# BSPD_rev11_v2.net
KiCad netlist of a schematic drawn in EAGLE
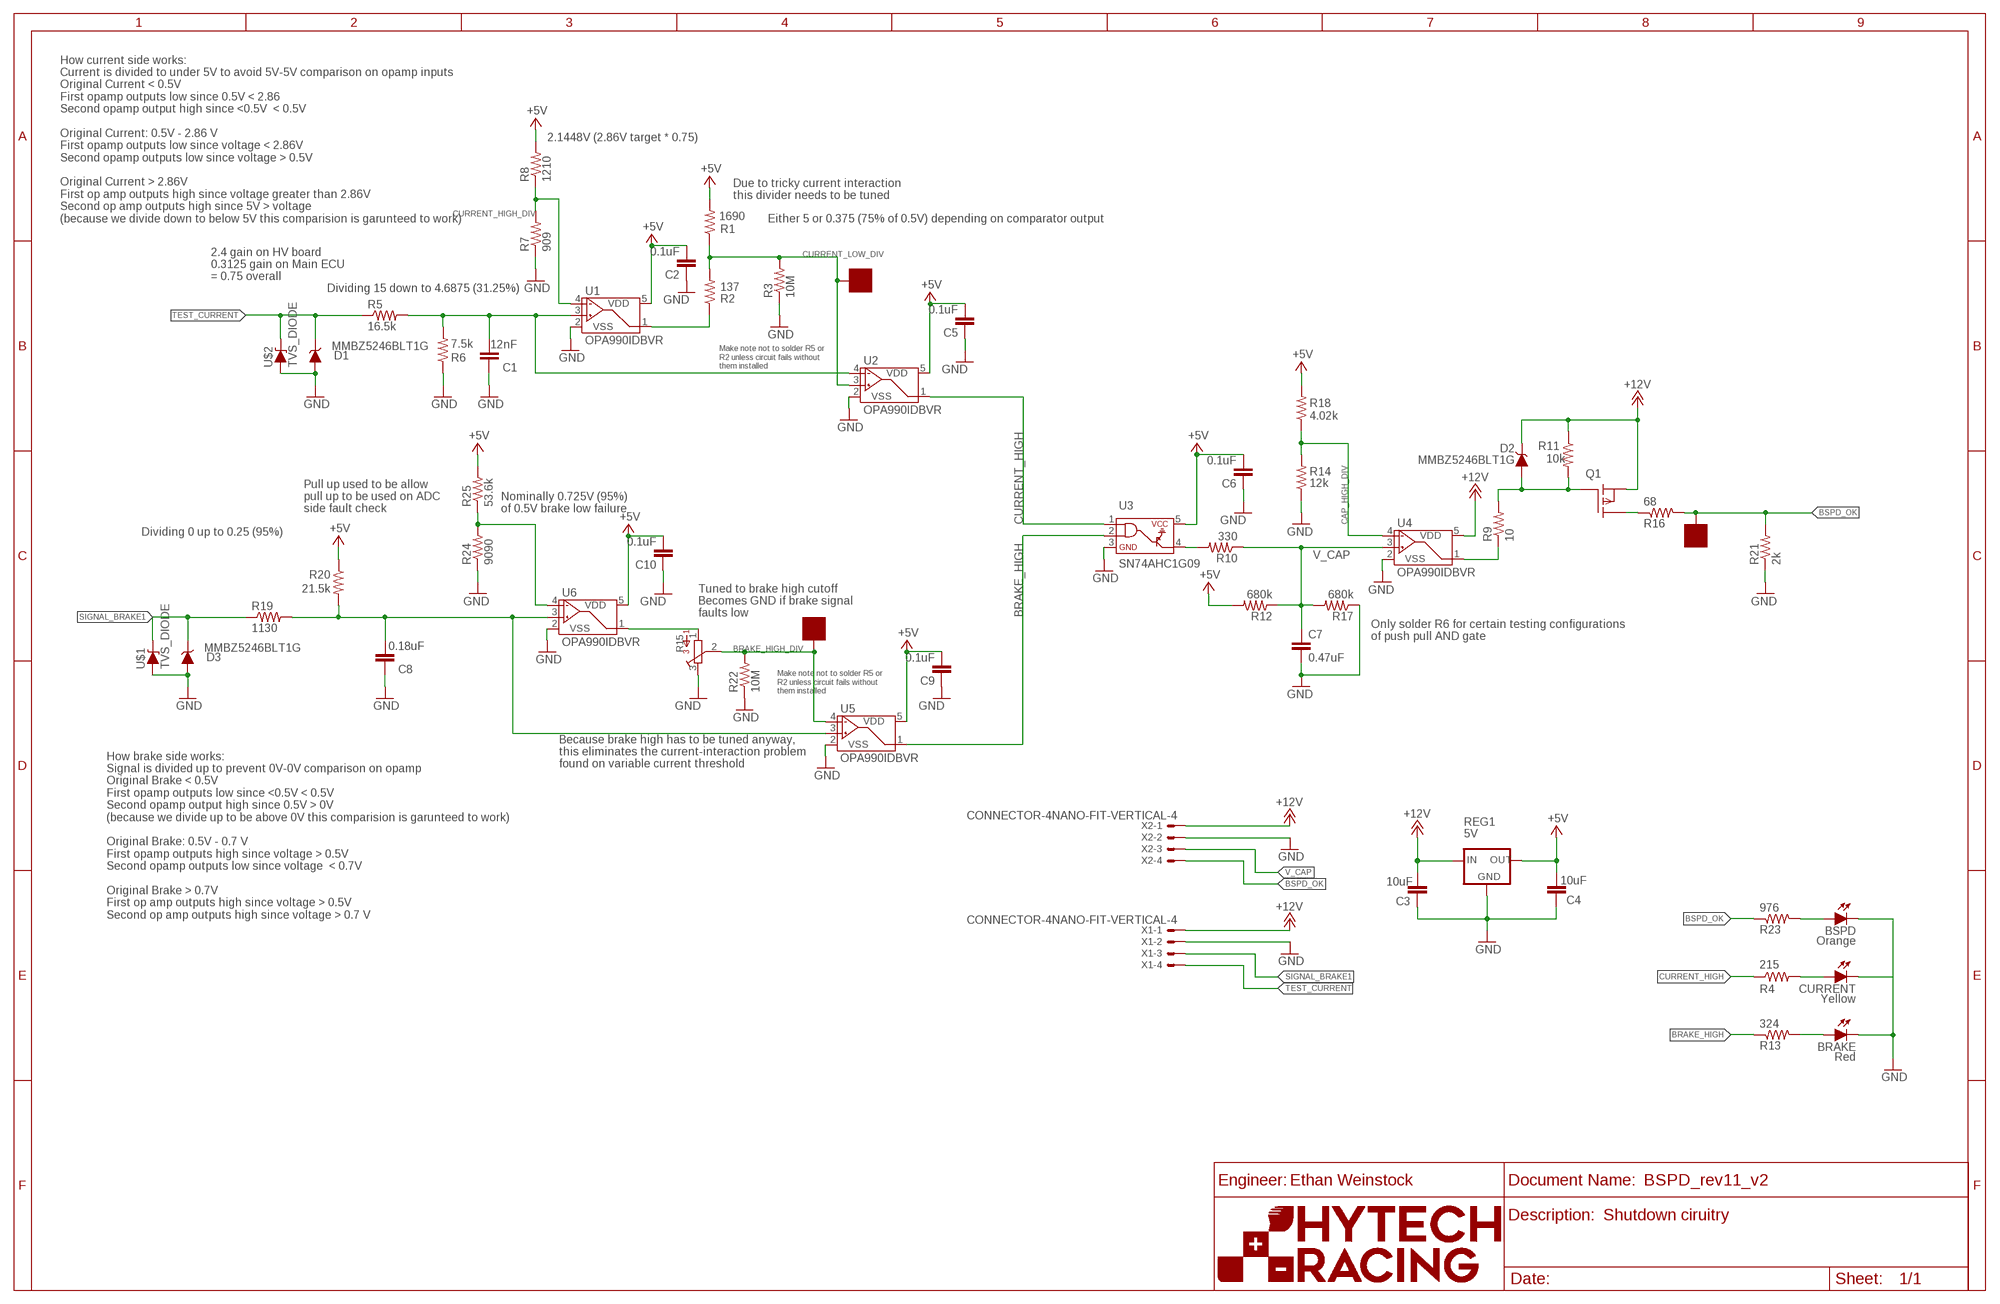
[diagram p0: schematic, sheet 1]

(export (version "E")
  (design (tool "Eeschema 10.0.6"))
  (components
    (comp (ref "BRAKE")
      (value "Red")
      (footprint "eagle-import:LED-603")
      (libsource (lib "eagle-import") (part "LED-0603"))
    )
    (comp (ref "BRAKE_LOW_DIV")
      (value "SOLDER_PAD")
      (footprint "eagle-import:SOLDER_PAD_XSMALL")
      (libsource (lib "eagle-import") (part "SOLDER_PAD"))
    )
    (comp (ref "BSPD")
      (value "Orange")
      (footprint "eagle-import:LED-603")
      (libsource (lib "eagle-import") (part "LED-0603"))
    )
    (comp (ref "BSPD_OK")
      (value "SOLDER_PAD")
      (footprint "eagle-import:SOLDER_PAD_XSMALL")
      (libsource (lib "eagle-import") (part "SOLDER_PAD"))
    )
    (comp (ref "C1")
      (value "12nF")
      (footprint "eagle-import:0603-CAP")
      (libsource (lib "eagle-import") (part "CAP0603-CAP"))
    )
    (comp (ref "C2")
      (value "0.1uF")
      (footprint "eagle-import:0603-CAP")
      (libsource (lib "eagle-import") (part "CAP0603-CAP"))
    )
    (comp (ref "C3")
      (value "10uF")
      (footprint "eagle-import:0603-CAP")
      (libsource (lib "eagle-import") (part "CAP0603-CAP"))
    )
    (comp (ref "C4")
      (value "10uF")
      (footprint "eagle-import:0603-CAP")
      (libsource (lib "eagle-import") (part "CAP0603-CAP"))
    )
    (comp (ref "C5")
      (value "0.1uF")
      (footprint "eagle-import:0603-CAP")
      (libsource (lib "eagle-import") (part "CAP0603-CAP"))
    )
    (comp (ref "C6")
      (value "0.1uF")
      (footprint "eagle-import:0603-CAP")
      (libsource (lib "eagle-import") (part "CAP0603-CAP"))
    )
    (comp (ref "C7")
      (value "0.47uF")
      (footprint "eagle-import:0603-CAP")
      (libsource (lib "eagle-import") (part "CAP0603-CAP"))
    )
    (comp (ref "C8")
      (value "0.18uF")
      (footprint "eagle-import:0603-CAP")
      (libsource (lib "eagle-import") (part "CAP0603-CAP"))
    )
    (comp (ref "C9")
      (value "0.1uF")
      (footprint "eagle-import:0603-CAP")
      (libsource (lib "eagle-import") (part "CAP0603-CAP"))
    )
    (comp (ref "C10")
      (value "0.1uF")
      (footprint "eagle-import:0603-CAP")
      (libsource (lib "eagle-import") (part "CAP0603-CAP"))
    )
    (comp (ref "CURRENT")
      (value "Yellow")
      (footprint "eagle-import:LED-603")
      (libsource (lib "eagle-import") (part "LED-0603"))
    )
    (comp (ref "CURRENT_LOW_DIV")
      (value "SOLDER_PAD")
      (footprint "eagle-import:SOLDER_PAD_XSMALL")
      (libsource (lib "eagle-import") (part "SOLDER_PAD"))
    )
    (comp (ref "D1")
      (value "MMBZ5246BLT1G")
      (footprint "eagle-import:SOT23")
      (libsource (lib "eagle-import") (part "DIODE_ZENER"))
    )
    (comp (ref "D2")
      (value "MMBZ5246BLT1G")
      (footprint "eagle-import:SOT23")
      (libsource (lib "eagle-import") (part "DIODE_ZENER"))
    )
    (comp (ref "D3")
      (value "MMBZ5246BLT1G")
      (footprint "eagle-import:SOT23")
      (libsource (lib "eagle-import") (part "DIODE_ZENER"))
    )
    (comp (ref "Q1")
      (value "P-CHANNEL_MOSFET_DMP3099L-7")
      (footprint "eagle-import:SOT23")
      (libsource (lib "eagle-import") (part "P-CHANNEL_MOSFET_DMP3099L-7"))
    )
    (comp (ref "R1")
      (value "1690")
      (footprint "eagle-import:0603-RES")
      (libsource (lib "eagle-import") (part "RESISTOR0603"))
    )
    (comp (ref "R2")
      (value "137")
      (footprint "eagle-import:0603-RES")
      (libsource (lib "eagle-import") (part "RESISTOR0603"))
    )
    (comp (ref "R3")
      (value "10M")
      (footprint "eagle-import:0603-RES")
      (libsource (lib "eagle-import") (part "RESISTOR0603"))
    )
    (comp (ref "R4")
      (value "215")
      (footprint "eagle-import:0603-RES")
      (libsource (lib "eagle-import") (part "RESISTOR0603"))
    )
    (comp (ref "R5")
      (value "16.5k")
      (footprint "eagle-import:0603-RES")
      (libsource (lib "eagle-import") (part "RESISTOR0603"))
    )
    (comp (ref "R6")
      (value "7.5k")
      (footprint "eagle-import:0603-RES")
      (libsource (lib "eagle-import") (part "RESISTOR0603"))
    )
    (comp (ref "R7")
      (value "909")
      (footprint "eagle-import:0603-RES")
      (libsource (lib "eagle-import") (part "RESISTOR0603"))
    )
    (comp (ref "R8")
      (value "1210")
      (footprint "eagle-import:0603-RES")
      (libsource (lib "eagle-import") (part "RESISTOR0603"))
    )
    (comp (ref "R9")
      (value "10")
      (footprint "eagle-import:0603-RES")
      (libsource (lib "eagle-import") (part "RESISTOR0603"))
    )
    (comp (ref "R10")
      (value "330")
      (footprint "eagle-import:0603-RES")
      (libsource (lib "eagle-import") (part "RESISTOR0603"))
    )
    (comp (ref "R11")
      (value "10k")
      (footprint "eagle-import:0603-RES")
      (libsource (lib "eagle-import") (part "RESISTOR0603"))
    )
    (comp (ref "R12")
      (value "680k")
      (footprint "eagle-import:0603-RES")
      (libsource (lib "eagle-import") (part "RESISTOR0603"))
    )
    (comp (ref "R13")
      (value "324")
      (footprint "eagle-import:0603-RES")
      (libsource (lib "eagle-import") (part "RESISTOR0603"))
    )
    (comp (ref "R14")
      (value "12k")
      (footprint "eagle-import:0603-RES")
      (libsource (lib "eagle-import") (part "RESISTOR0603"))
    )
    (comp (ref "R15")
      (value "TRIMPOT_3296C")
      (footprint "eagle-import:TRIMPOT_3296")
      (libsource (lib "eagle-import") (part "TRIMPOT_3296C"))
    )
    (comp (ref "R16")
      (value "68")
      (footprint "eagle-import:0603-RES")
      (libsource (lib "eagle-import") (part "RESISTOR0603"))
    )
    (comp (ref "R17")
      (value "680k")
      (footprint "eagle-import:0603-RES")
      (libsource (lib "eagle-import") (part "RESISTOR0603"))
    )
    (comp (ref "R18")
      (value "4.02k")
      (footprint "eagle-import:0603-RES")
      (libsource (lib "eagle-import") (part "RESISTOR0603"))
    )
    (comp (ref "R19")
      (value "1130")
      (footprint "eagle-import:0603-RES")
      (libsource (lib "eagle-import") (part "RESISTOR0603"))
    )
    (comp (ref "R20")
      (value "21.5k")
      (footprint "eagle-import:0603-RES")
      (libsource (lib "eagle-import") (part "RESISTOR0603"))
    )
    (comp (ref "R21")
      (value "2k")
      (footprint "eagle-import:0603-RES")
      (libsource (lib "eagle-import") (part "RESISTOR0603"))
    )
    (comp (ref "R22")
      (value "10M")
      (footprint "eagle-import:0603-RES")
      (libsource (lib "eagle-import") (part "RESISTOR0603"))
    )
    (comp (ref "R23")
      (value "976")
      (footprint "eagle-import:0603-RES")
      (libsource (lib "eagle-import") (part "RESISTOR0603"))
    )
    (comp (ref "R24")
      (value "9090")
      (footprint "eagle-import:0603-RES")
      (libsource (lib "eagle-import") (part "RESISTOR0603"))
    )
    (comp (ref "R25")
      (value "53.6k")
      (footprint "eagle-import:0603-RES")
      (libsource (lib "eagle-import") (part "RESISTOR0603"))
    )
    (comp (ref "REG1")
      (value "5V")
      (footprint "eagle-import:OKI-78SR")
      (libsource (lib "eagle-import") (part "OKI-78SR-5"))
    )
    (comp (ref "U$1")
      (value "TVS_DIODE")
      (footprint "eagle-import:U-DFN1608-2")
      (libsource (lib "eagle-import") (part "TVS_DIODE"))
    )
    (comp (ref "U$2")
      (value "TVS_DIODE")
      (footprint "eagle-import:U-DFN1608-2")
      (libsource (lib "eagle-import") (part "TVS_DIODE"))
    )
    (comp (ref "U1")
      (value "OPA990IDBVR")
      (footprint "eagle-import:SOT-23-5")
      (libsource (lib "eagle-import") (part "OPA990IDBVR"))
    )
    (comp (ref "U2")
      (value "OPA990IDBVR")
      (footprint "eagle-import:SOT-23-5")
      (libsource (lib "eagle-import") (part "OPA990IDBVR"))
    )
    (comp (ref "U3")
      (value "SN74AHC1G09")
      (footprint "eagle-import:SOT-23-5")
      (libsource (lib "eagle-import") (part "SN74AHC1G09"))
    )
    (comp (ref "U4")
      (value "OPA990IDBVR")
      (footprint "eagle-import:SOT-23-5")
      (libsource (lib "eagle-import") (part "OPA990IDBVR"))
    )
    (comp (ref "U5")
      (value "OPA990IDBVR")
      (footprint "eagle-import:SOT-23-5")
      (libsource (lib "eagle-import") (part "OPA990IDBVR"))
    )
    (comp (ref "U6")
      (value "OPA990IDBVR")
      (footprint "eagle-import:SOT-23-5")
      (libsource (lib "eagle-import") (part "OPA990IDBVR"))
    )
    (comp (ref "X1")
      (value "CONNECTOR-4NANO-FIT-VERTICAL-4")
      (footprint "eagle-import:NANO-FIT_VERTICAL-4")
      (libsource (lib "eagle-import") (part "CONNECTOR-4NANO-FIT-VERTICAL-4"))
    )
    (comp (ref "X2")
      (value "CONNECTOR-4NANO-FIT-VERTICAL-4")
      (footprint "eagle-import:NANO-FIT_VERTICAL-4")
      (libsource (lib "eagle-import") (part "CONNECTOR-4NANO-FIT-VERTICAL-4"))
    )
  )
  (nets
    (net (code "1") (name "+5V") (class "Default")
      (node (ref "C10") (pin "2") (pinfunction "2_2") (pintype "passive"))
      (node (ref "C2") (pin "2") (pinfunction "2_2") (pintype "passive"))
      (node (ref "C4") (pin "2") (pinfunction "2_2") (pintype "passive"))
      (node (ref "C5") (pin "2") (pinfunction "2_2") (pintype "passive"))
      (node (ref "C6") (pin "2") (pinfunction "2_2") (pintype "passive"))
      (node (ref "C9") (pin "2") (pinfunction "2_2") (pintype "passive"))
      (node (ref "R1") (pin "2") (pinfunction "2_2") (pintype "passive"))
      (node (ref "R12") (pin "2") (pinfunction "2_2") (pintype "passive"))
      (node (ref "R18") (pin "2") (pinfunction "2_2") (pintype "passive"))
      (node (ref "R20") (pin "1") (pinfunction "1_1") (pintype "passive"))
      (node (ref "R25") (pin "2") (pinfunction "2_2") (pintype "passive"))
      (node (ref "R8") (pin "2") (pinfunction "2_2") (pintype "passive"))
      (node (ref "REG1") (pin "3") (pinfunction "OUT_3") (pintype "passive"))
      (node (ref "U1") (pin "5") (pinfunction "VDD_5") (pintype "passive"))
      (node (ref "U2") (pin "5") (pinfunction "VDD_5") (pintype "passive"))
      (node (ref "U3") (pin "5") (pinfunction "5_5") (pintype "passive"))
      (node (ref "U5") (pin "5") (pinfunction "VDD_5") (pintype "passive"))
      (node (ref "U6") (pin "5") (pinfunction "VDD_5") (pintype "passive"))
    )
    (net (code "2") (name "+12V") (class "Default")
      (node (ref "C3") (pin "2") (pinfunction "2_2") (pintype "passive"))
      (node (ref "D2") (pin "3") (pinfunction "C_3") (pintype "passive"))
      (node (ref "Q1") (pin "2") (pinfunction "S_2") (pintype "passive"))
      (node (ref "R11") (pin "1") (pinfunction "1_1") (pintype "passive"))
      (node (ref "REG1") (pin "1") (pinfunction "IN_1") (pintype "input"))
      (node (ref "U4") (pin "5") (pinfunction "VDD_5") (pintype "passive"))
      (node (ref "X1") (pin "P$1") (pinfunction "S_P$1") (pintype "passive"))
      (node (ref "X2") (pin "P$1") (pinfunction "S_P$1") (pintype "passive"))
    )
    (net (code "3") (name "/BRAKE_HIGH_DIV") (class "Default")
      (node (ref "BRAKE_LOW_DIV") (pin "P$1") (pinfunction "P$1_P$1") (pintype "bidirectional"))
      (node (ref "R15") (pin "2") (pinfunction "2_2") (pintype "passive"))
      (node (ref "R22") (pin "2") (pinfunction "2_2") (pintype "passive"))
      (node (ref "U5") (pin "4") (pinfunction "VIN-_4") (pintype "passive"))
    )
    (net (code "4") (name "/CAP_HIGH_DIV") (class "Default")
      (node (ref "R14") (pin "2") (pinfunction "2_2") (pintype "passive"))
      (node (ref "R18") (pin "1") (pinfunction "1_1") (pintype "passive"))
      (node (ref "U4") (pin "4") (pinfunction "VIN-_4") (pintype "passive"))
    )
    (net (code "5") (name "/CURRENT_HIGH_DIV") (class "Default")
      (node (ref "R7") (pin "2") (pinfunction "2_2") (pintype "passive"))
      (node (ref "R8") (pin "1") (pinfunction "1_1") (pintype "passive"))
      (node (ref "U1") (pin "4") (pinfunction "VIN-_4") (pintype "passive"))
    )
    (net (code "6") (name "/CURRENT_LOW_DIV") (class "Default")
      (node (ref "CURRENT_LOW_DIV") (pin "P$1") (pinfunction "P$1_P$1") (pintype "bidirectional"))
      (node (ref "R1") (pin "1") (pinfunction "1_1") (pintype "passive"))
      (node (ref "R2") (pin "2") (pinfunction "2_2") (pintype "passive"))
      (node (ref "R3") (pin "2") (pinfunction "2_2") (pintype "passive"))
      (node (ref "U2") (pin "3") (pinfunction "VIN+_3") (pintype "passive"))
    )
    (net (code "7") (name "BRAKE_HIGH") (class "Default")
      (node (ref "R13") (pin "1") (pinfunction "1_1") (pintype "passive"))
      (node (ref "U3") (pin "2") (pinfunction "2_2") (pintype "passive"))
      (node (ref "U5") (pin "1") (pinfunction "VOUT_1") (pintype "passive"))
    )
    (net (code "8") (name "BSPD_OK") (class "Default")
      (node (ref "BSPD_OK") (pin "P$1") (pinfunction "P$1_P$1") (pintype "bidirectional"))
      (node (ref "R16") (pin "2") (pinfunction "2_2") (pintype "passive"))
      (node (ref "R21") (pin "2") (pinfunction "2_2") (pintype "passive"))
      (node (ref "R23") (pin "1") (pinfunction "1_1") (pintype "passive"))
      (node (ref "X2") (pin "P$4") (pinfunction "S_P$4") (pintype "passive"))
    )
    (net (code "9") (name "CURRENT_HIGH") (class "Default")
      (node (ref "R4") (pin "1") (pinfunction "1_1") (pintype "passive"))
      (node (ref "U2") (pin "1") (pinfunction "VOUT_1") (pintype "passive"))
      (node (ref "U3") (pin "1") (pinfunction "1_1") (pintype "passive"))
    )
    (net (code "10") (name "GND") (class "Default")
      (node (ref "BRAKE") (pin "C") (pinfunction "C_C") (pintype "passive"))
      (node (ref "BSPD") (pin "C") (pinfunction "C_C") (pintype "passive"))
      (node (ref "C1") (pin "1") (pinfunction "1_1") (pintype "passive"))
      (node (ref "C10") (pin "1") (pinfunction "1_1") (pintype "passive"))
      (node (ref "C2") (pin "1") (pinfunction "1_1") (pintype "passive"))
      (node (ref "C3") (pin "1") (pinfunction "1_1") (pintype "passive"))
      (node (ref "C4") (pin "1") (pinfunction "1_1") (pintype "passive"))
      (node (ref "C5") (pin "1") (pinfunction "1_1") (pintype "passive"))
      (node (ref "C6") (pin "1") (pinfunction "1_1") (pintype "passive"))
      (node (ref "C7") (pin "2") (pinfunction "2_2") (pintype "passive"))
      (node (ref "C8") (pin "1") (pinfunction "1_1") (pintype "passive"))
      (node (ref "C9") (pin "1") (pinfunction "1_1") (pintype "passive"))
      (node (ref "CURRENT") (pin "C") (pinfunction "C_C") (pintype "passive"))
      (node (ref "D1") (pin "1") (pinfunction "A_1") (pintype "passive"))
      (node (ref "D3") (pin "1") (pinfunction "A_1") (pintype "passive"))
      (node (ref "R14") (pin "1") (pinfunction "1_1") (pintype "passive"))
      (node (ref "R15") (pin "3") (pinfunction "3_3") (pintype "passive"))
      (node (ref "R17") (pin "1") (pinfunction "1_1") (pintype "passive"))
      (node (ref "R21") (pin "1") (pinfunction "1_1") (pintype "passive"))
      (node (ref "R22") (pin "1") (pinfunction "1_1") (pintype "passive"))
      (node (ref "R24") (pin "1") (pinfunction "1_1") (pintype "passive"))
      (node (ref "R3") (pin "1") (pinfunction "1_1") (pintype "passive"))
      (node (ref "R6") (pin "1") (pinfunction "1_1") (pintype "passive"))
      (node (ref "R7") (pin "1") (pinfunction "1_1") (pintype "passive"))
      (node (ref "REG1") (pin "2") (pinfunction "GND_2") (pintype "input"))
      (node (ref "U$1") (pin "P$1") (pinfunction "A_P$1") (pintype "passive"))
      (node (ref "U$2") (pin "P$1") (pinfunction "A_P$1") (pintype "passive"))
      (node (ref "U1") (pin "2") (pinfunction "VSS_2") (pintype "passive"))
      (node (ref "U2") (pin "2") (pinfunction "VSS_2") (pintype "passive"))
      (node (ref "U3") (pin "3") (pinfunction "3_3") (pintype "passive"))
      (node (ref "U4") (pin "2") (pinfunction "VSS_2") (pintype "passive"))
      (node (ref "U5") (pin "2") (pinfunction "VSS_2") (pintype "passive"))
      (node (ref "U6") (pin "2") (pinfunction "VSS_2") (pintype "passive"))
      (node (ref "X1") (pin "P$2") (pinfunction "S_P$2") (pintype "passive"))
      (node (ref "X2") (pin "P$2") (pinfunction "S_P$2") (pintype "passive"))
    )
    (net (code "11") (name "Net-(BRAKE-PadA)") (class "Default")
      (node (ref "BRAKE") (pin "A") (pinfunction "A_A") (pintype "passive"))
      (node (ref "R13") (pin "2") (pinfunction "2_2") (pintype "passive"))
    )
    (net (code "12") (name "Net-(BSPD-PadA)") (class "Default")
      (node (ref "BSPD") (pin "A") (pinfunction "A_A") (pintype "passive"))
      (node (ref "R23") (pin "2") (pinfunction "2_2") (pintype "passive"))
    )
    (net (code "13") (name "Net-(CURRENT-PadA)") (class "Default")
      (node (ref "CURRENT") (pin "A") (pinfunction "A_A") (pintype "passive"))
      (node (ref "R4") (pin "2") (pinfunction "2_2") (pintype "passive"))
    )
    (net (code "14") (name "Net-(D2-A)") (class "Default")
      (node (ref "D2") (pin "1") (pinfunction "A_1") (pintype "passive"))
      (node (ref "Q1") (pin "1") (pinfunction "G_1") (pintype "passive"))
      (node (ref "R11") (pin "2") (pinfunction "2_2") (pintype "passive"))
      (node (ref "R9") (pin "2") (pinfunction "2_2") (pintype "passive"))
    )
    (net (code "15") (name "Net-(Q1-D)") (class "Default")
      (node (ref "Q1") (pin "3") (pinfunction "D_3") (pintype "passive"))
      (node (ref "R16") (pin "1") (pinfunction "1_1") (pintype "passive"))
    )
    (net (code "16") (name "Net-(R10-Pad2)") (class "Default")
      (node (ref "R10") (pin "2") (pinfunction "2_2") (pintype "passive"))
      (node (ref "U3") (pin "4") (pinfunction "4_4") (pintype "passive"))
    )
    (net (code "17") (name "Net-(U1-VIN+)") (class "Default")
      (node (ref "C1") (pin "2") (pinfunction "2_2") (pintype "passive"))
      (node (ref "R5") (pin "2") (pinfunction "2_2") (pintype "passive"))
      (node (ref "R6") (pin "2") (pinfunction "2_2") (pintype "passive"))
      (node (ref "U1") (pin "3") (pinfunction "VIN+_3") (pintype "passive"))
      (node (ref "U2") (pin "4") (pinfunction "VIN-_4") (pintype "passive"))
    )
    (net (code "18") (name "Net-(U1-VOUT)") (class "Default")
      (node (ref "R2") (pin "1") (pinfunction "1_1") (pintype "passive"))
      (node (ref "U1") (pin "1") (pinfunction "VOUT_1") (pintype "passive"))
    )
    (net (code "19") (name "Net-(U4-VOUT)") (class "Default")
      (node (ref "R9") (pin "1") (pinfunction "1_1") (pintype "passive"))
      (node (ref "U4") (pin "1") (pinfunction "VOUT_1") (pintype "passive"))
    )
    (net (code "20") (name "Net-(U5-VIN+)") (class "Default")
      (node (ref "C8") (pin "2") (pinfunction "2_2") (pintype "passive"))
      (node (ref "R19") (pin "2") (pinfunction "2_2") (pintype "passive"))
      (node (ref "R20") (pin "2") (pinfunction "2_2") (pintype "passive"))
      (node (ref "U5") (pin "3") (pinfunction "VIN+_3") (pintype "passive"))
      (node (ref "U6") (pin "3") (pinfunction "VIN+_3") (pintype "passive"))
    )
    (net (code "21") (name "Net-(U6-VIN-)") (class "Default")
      (node (ref "R24") (pin "2") (pinfunction "2_2") (pintype "passive"))
      (node (ref "R25") (pin "1") (pinfunction "1_1") (pintype "passive"))
      (node (ref "U6") (pin "4") (pinfunction "VIN-_4") (pintype "passive"))
    )
    (net (code "22") (name "Net-(U6-VOUT)") (class "Default")
      (node (ref "R15") (pin "1") (pinfunction "1_1") (pintype "passive"))
      (node (ref "U6") (pin "1") (pinfunction "VOUT_1") (pintype "passive"))
    )
    (net (code "23") (name "SIGNAL_BRAKE1") (class "Default")
      (node (ref "D3") (pin "3") (pinfunction "C_3") (pintype "passive"))
      (node (ref "R19") (pin "1") (pinfunction "1_1") (pintype "passive"))
      (node (ref "U$1") (pin "P$2") (pinfunction "C_P$2") (pintype "passive"))
      (node (ref "X1") (pin "P$3") (pinfunction "S_P$3") (pintype "passive"))
    )
    (net (code "24") (name "TEST_CURRENT") (class "Default")
      (node (ref "D1") (pin "3") (pinfunction "C_3") (pintype "passive"))
      (node (ref "R5") (pin "1") (pinfunction "1_1") (pintype "passive"))
      (node (ref "U$2") (pin "P$2") (pinfunction "C_P$2") (pintype "passive"))
      (node (ref "X1") (pin "P$4") (pinfunction "S_P$4") (pintype "passive"))
    )
    (net (code "25") (name "V_CAP") (class "Default")
      (node (ref "C7") (pin "1") (pinfunction "1_1") (pintype "passive"))
      (node (ref "R10") (pin "1") (pinfunction "1_1") (pintype "passive"))
      (node (ref "R12") (pin "1") (pinfunction "1_1") (pintype "passive"))
      (node (ref "R17") (pin "2") (pinfunction "2_2") (pintype "passive"))
      (node (ref "U4") (pin "3") (pinfunction "VIN+_3") (pintype "passive"))
      (node (ref "X2") (pin "P$3") (pinfunction "S_P$3") (pintype "passive"))
    )
  )
)
